# BpodFSM_r2_5_v6.net
KiCad netlist of a schematic drawn in EAGLE
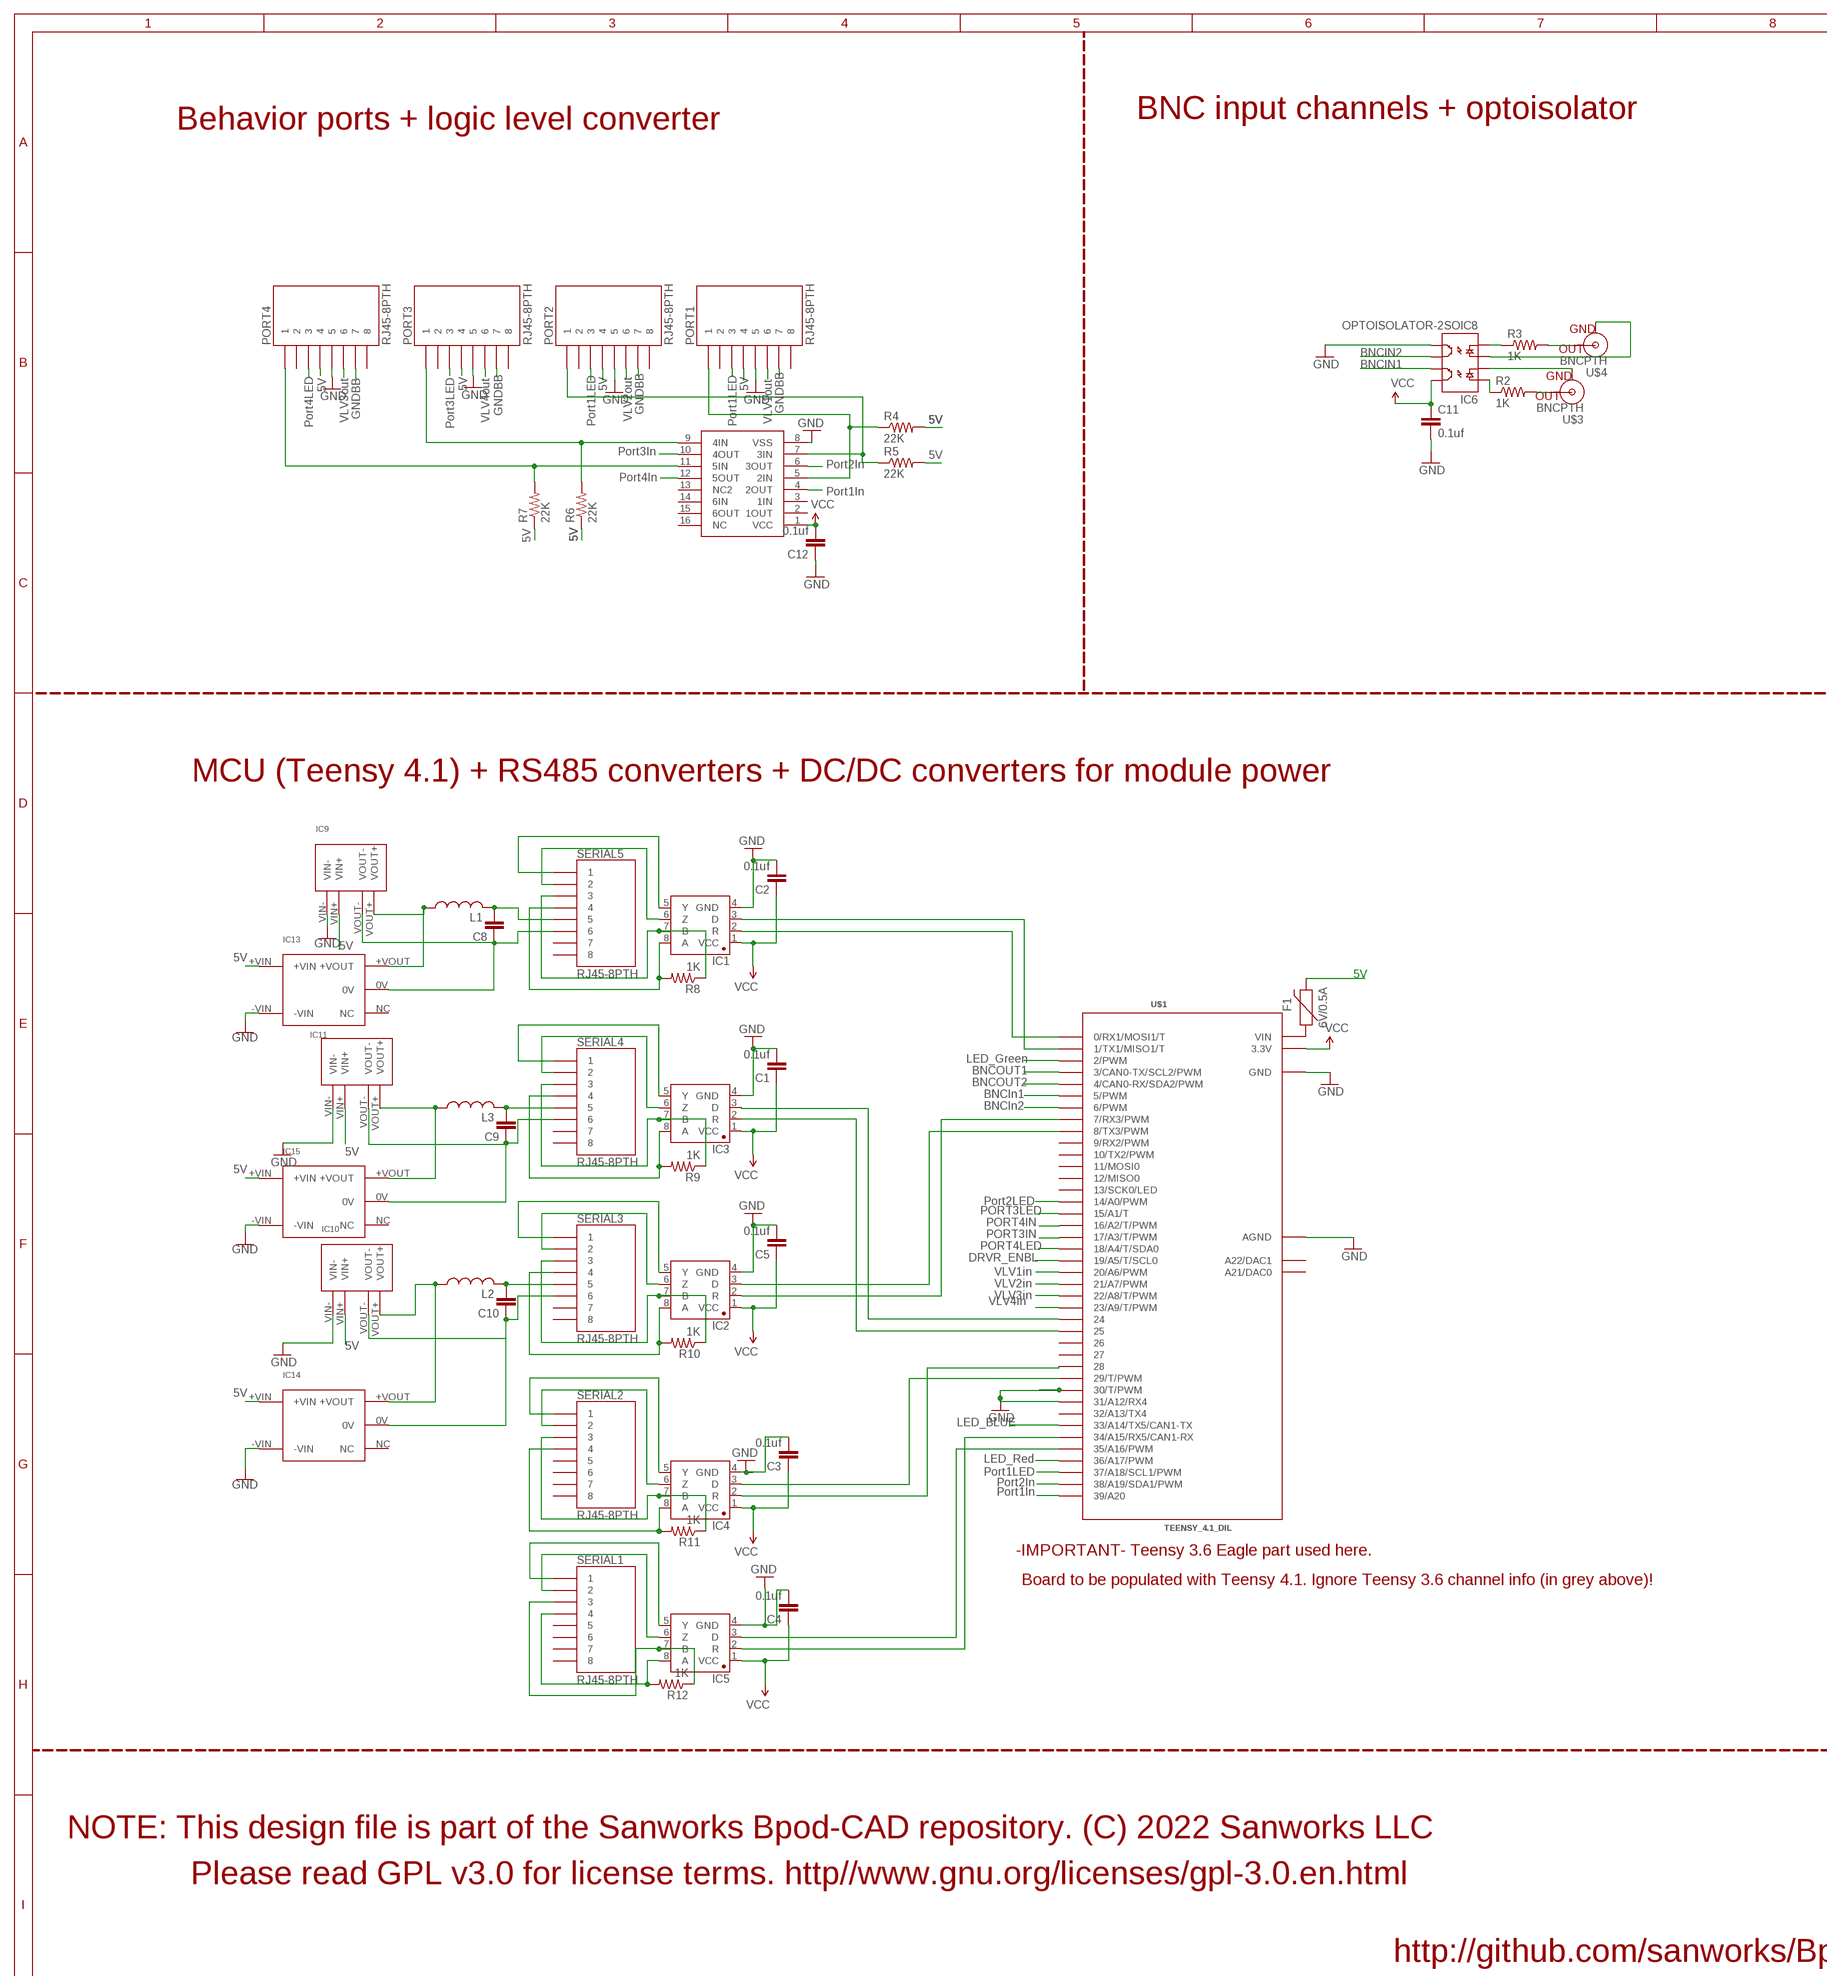
[diagram p0: schematic, sheet 1, part 1 of 2]
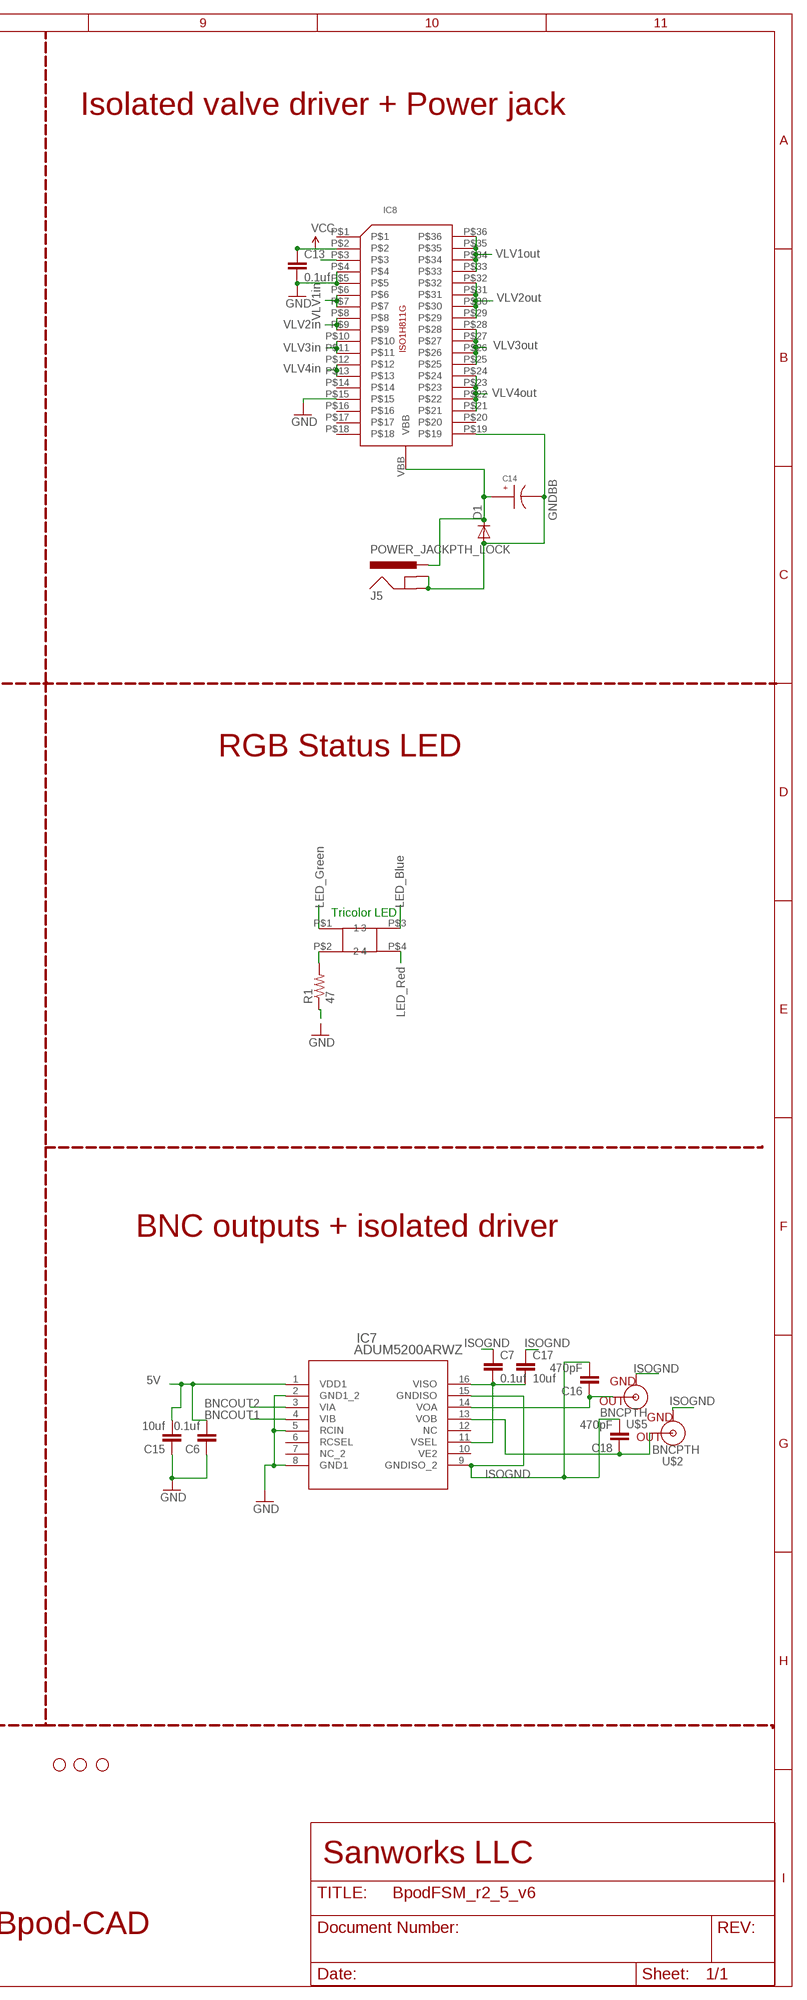
[diagram p1: schematic, sheet 1, part 2 of 2]

(export (version "E")
  (design (tool "Eeschema 10.0.6"))
  (components
    (comp (ref "C1")
      (value "0.1uf")
      (footprint "eagle-import:1206@1")
      (libsource (lib "eagle-import") (part "CAP1206"))
    )
    (comp (ref "C2")
      (value "0.1uf")
      (footprint "eagle-import:1206@1")
      (libsource (lib "eagle-import") (part "CAP1206"))
    )
    (comp (ref "C3")
      (value "0.1uf")
      (footprint "eagle-import:1206@1")
      (libsource (lib "eagle-import") (part "CAP1206"))
    )
    (comp (ref "C4")
      (value "0.1uf")
      (footprint "eagle-import:1206@1")
      (libsource (lib "eagle-import") (part "CAP1206"))
    )
    (comp (ref "C5")
      (value "0.1uf")
      (footprint "eagle-import:1206@1")
      (libsource (lib "eagle-import") (part "CAP1206"))
    )
    (comp (ref "C6")
      (value "0.1uf")
      (footprint "eagle-import:0805")
      (libsource (lib "eagle-import") (part "1.0UF-0805-25V-10%"))
    )
    (comp (ref "C7")
      (value "0.1uf")
      (footprint "eagle-import:0805")
      (libsource (lib "eagle-import") (part "1.0UF-0805-25V-10%"))
    )
    (comp (ref "C8")
      (value "CAP1206")
      (footprint "eagle-import:1206@1")
      (libsource (lib "eagle-import") (part "CAP1206"))
    )
    (comp (ref "C9")
      (value "CAP1206")
      (footprint "eagle-import:1206@1")
      (libsource (lib "eagle-import") (part "CAP1206"))
    )
    (comp (ref "C10")
      (value "CAP1206")
      (footprint "eagle-import:1206@1")
      (libsource (lib "eagle-import") (part "CAP1206"))
    )
    (comp (ref "C11")
      (value "0.1uf")
      (footprint "eagle-import:1206@1")
      (libsource (lib "eagle-import") (part "CAP1206"))
    )
    (comp (ref "C12")
      (value "0.1uf")
      (footprint "eagle-import:1206@1")
      (libsource (lib "eagle-import") (part "CAP1206"))
    )
    (comp (ref "C13")
      (value "0.1uf")
      (footprint "eagle-import:1206@1")
      (libsource (lib "eagle-import") (part "CAP1206"))
    )
    (comp (ref "C14")
      (value "EEE-FK1H100UR")
      (footprint "eagle-import:EEE-FK1H100UR")
      (libsource (lib "eagle-import") (part "EEE-FK1H100UR"))
    )
    (comp (ref "C15")
      (value "10uf")
      (footprint "eagle-import:1206@1")
      (libsource (lib "eagle-import") (part "CAP1206"))
    )
    (comp (ref "C16")
      (value "470pF")
      (footprint "eagle-import:0805")
      (libsource (lib "eagle-import") (part "1.0UF-0805-25V-10%"))
    )
    (comp (ref "C17")
      (value "10uf")
      (footprint "eagle-import:1206@1")
      (libsource (lib "eagle-import") (part "CAP1206"))
    )
    (comp (ref "C18")
      (value "470pF")
      (footprint "eagle-import:0805")
      (libsource (lib "eagle-import") (part "1.0UF-0805-25V-10%"))
    )
    (comp (ref "D1")
      (value "DIODE-DO214AA")
      (footprint "eagle-import:DO214AA")
      (libsource (lib "eagle-import") (part "DIODE-DO214AA"))
    )
    (comp (ref "F1")
      (value "6V/0.5A")
      (footprint "eagle-import:1206")
      (libsource (lib "eagle-import") (part "PPTC_HALF-AMP"))
    )
    (comp (ref "IC1")
      (value "SN65HVD31DR")
      (footprint "eagle-import:SO08")
      (libsource (lib "eagle-import") (part "SN65HVD31DR"))
    )
    (comp (ref "IC2")
      (value "SN65HVD31DR")
      (footprint "eagle-import:SO08")
      (libsource (lib "eagle-import") (part "SN65HVD31DR"))
    )
    (comp (ref "IC3")
      (value "SN65HVD31DR")
      (footprint "eagle-import:SO08")
      (libsource (lib "eagle-import") (part "SN65HVD31DR"))
    )
    (comp (ref "IC4")
      (value "SN65HVD31DR")
      (footprint "eagle-import:SO08")
      (libsource (lib "eagle-import") (part "SN65HVD31DR"))
    )
    (comp (ref "IC5")
      (value "SN65HVD31DR")
      (footprint "eagle-import:SO08")
      (libsource (lib "eagle-import") (part "SN65HVD31DR"))
    )
    (comp (ref "IC6")
      (value "OPTOISOLATOR-2SOIC8")
      (footprint "eagle-import:SO08-2")
      (libsource (lib "eagle-import") (part "OPTOISOLATOR-2SOIC8"))
    )
    (comp (ref "IC7")
      (value "ADUM5200ARWZ")
      (footprint "eagle-import:RW_16")
      (libsource (lib "eagle-import") (part "ADUM5200ARWZ"))
    )
    (comp (ref "IC8")
      (value "ISO1H811G")
      (footprint "eagle-import:ISO1H811G")
      (libsource (lib "eagle-import") (part "ISO1H811G"))
    )
    (comp (ref "IC9")
      (value "NME0509SC")
      (footprint "eagle-import:NME0509SC")
      (libsource (lib "eagle-import") (part "NME0509SC"))
    )
    (comp (ref "IC10")
      (value "NME0509SC")
      (footprint "eagle-import:NME0509SC")
      (libsource (lib "eagle-import") (part "NME0509SC"))
    )
    (comp (ref "IC11")
      (value "NME0509SC")
      (footprint "eagle-import:NME0509SC")
      (libsource (lib "eagle-import") (part "NME0509SC"))
    )
    (comp (ref "IC12")
      (value "CD4050")
      (footprint "eagle-import:SO16")
      (libsource (lib "eagle-import") (part "CD4050"))
    )
    (comp (ref "IC13")
      (value "MTU1D0505MC")
      (footprint "eagle-import:MTU1D0505MC")
      (libsource (lib "eagle-import") (part "MTU1D0505MC"))
    )
    (comp (ref "IC14")
      (value "MTU1D0505MC")
      (footprint "eagle-import:MTU1D0505MC")
      (libsource (lib "eagle-import") (part "MTU1D0505MC"))
    )
    (comp (ref "IC15")
      (value "MTU1D0505MC")
      (footprint "eagle-import:MTU1D0505MC")
      (libsource (lib "eagle-import") (part "MTU1D0505MC"))
    )
    (comp (ref "J5")
      (value "POWER_JACKPTH_LOCK")
      (footprint "eagle-import:POWER_JACK_PTH_LOCK")
      (libsource (lib "eagle-import") (part "POWER_JACKPTH_LOCK"))
    )
    (comp (ref "JP3")
      (value "STAND-OFF")
      (footprint "eagle-import:STAND-OFF")
      (libsource (lib "eagle-import") (part "STAND-OFF"))
    )
    (comp (ref "JP4")
      (value "STAND-OFF")
      (footprint "eagle-import:STAND-OFF")
      (libsource (lib "eagle-import") (part "STAND-OFF"))
    )
    (comp (ref "JP5")
      (value "STAND-OFF")
      (footprint "eagle-import:STAND-OFF")
      (libsource (lib "eagle-import") (part "STAND-OFF"))
    )
    (comp (ref "L1")
      (value "L-USL3225M")
      (footprint "eagle-import:L3225M")
      (libsource (lib "eagle-import") (part "L-USL3225M"))
    )
    (comp (ref "L2")
      (value "L-USL3225M")
      (footprint "eagle-import:L3225M")
      (libsource (lib "eagle-import") (part "L-USL3225M"))
    )
    (comp (ref "L3")
      (value "L-USL3225M")
      (footprint "eagle-import:L3225M")
      (libsource (lib "eagle-import") (part "L-USL3225M"))
    )
    (comp (ref "PORT1")
      (value "RJ45-8PTH")
      (footprint "eagle-import:RJ45-8")
      (libsource (lib "eagle-import") (part "RJ45-8PTH"))
    )
    (comp (ref "PORT2")
      (value "RJ45-8PTH")
      (footprint "eagle-import:RJ45-8")
      (libsource (lib "eagle-import") (part "RJ45-8PTH"))
    )
    (comp (ref "PORT3")
      (value "RJ45-8PTH")
      (footprint "eagle-import:RJ45-8")
      (libsource (lib "eagle-import") (part "RJ45-8PTH"))
    )
    (comp (ref "PORT4")
      (value "RJ45-8PTH")
      (footprint "eagle-import:RJ45-8")
      (libsource (lib "eagle-import") (part "RJ45-8PTH"))
    )
    (comp (ref "R1")
      (value "47")
      (footprint "eagle-import:1206")
      (libsource (lib "eagle-import") (part "RESISTOR1206"))
    )
    (comp (ref "R2")
      (value "1K")
      (footprint "eagle-import:1206")
      (libsource (lib "eagle-import") (part "SparkFun-Resistors_RESISTOR1206"))
    )
    (comp (ref "R3")
      (value "1K")
      (footprint "eagle-import:1206")
      (libsource (lib "eagle-import") (part "SparkFun-Resistors_RESISTOR1206"))
    )
    (comp (ref "R4")
      (value "22K")
      (footprint "eagle-import:1206")
      (libsource (lib "eagle-import") (part "SparkFun-Resistors_RESISTOR1206"))
    )
    (comp (ref "R5")
      (value "22K")
      (footprint "eagle-import:1206")
      (libsource (lib "eagle-import") (part "SparkFun-Resistors_RESISTOR1206"))
    )
    (comp (ref "R6")
      (value "22K")
      (footprint "eagle-import:1206")
      (libsource (lib "eagle-import") (part "SparkFun-Resistors_RESISTOR1206"))
    )
    (comp (ref "R7")
      (value "22K")
      (footprint "eagle-import:1206")
      (libsource (lib "eagle-import") (part "SparkFun-Resistors_RESISTOR1206"))
    )
    (comp (ref "R8")
      (value "1K")
      (footprint "eagle-import:1206")
      (libsource (lib "eagle-import") (part "SparkFun-Resistors_RESISTOR1206"))
    )
    (comp (ref "R9")
      (value "1K")
      (footprint "eagle-import:1206")
      (libsource (lib "eagle-import") (part "SparkFun-Resistors_RESISTOR1206"))
    )
    (comp (ref "R10")
      (value "1K")
      (footprint "eagle-import:1206")
      (libsource (lib "eagle-import") (part "SparkFun-Resistors_RESISTOR1206"))
    )
    (comp (ref "R11")
      (value "1K")
      (footprint "eagle-import:1206")
      (libsource (lib "eagle-import") (part "SparkFun-Resistors_RESISTOR1206"))
    )
    (comp (ref "R12")
      (value "1K")
      (footprint "eagle-import:1206")
      (libsource (lib "eagle-import") (part "SparkFun-Resistors_RESISTOR1206"))
    )
    (comp (ref "SERIAL1")
      (value "RJ45-8PTH")
      (footprint "eagle-import:RJ45-8")
      (libsource (lib "eagle-import") (part "RJ45-8PTH"))
    )
    (comp (ref "SERIAL2")
      (value "RJ45-8PTH")
      (footprint "eagle-import:RJ45-8")
      (libsource (lib "eagle-import") (part "RJ45-8PTH"))
    )
    (comp (ref "SERIAL3")
      (value "RJ45-8PTH")
      (footprint "eagle-import:RJ45-8")
      (libsource (lib "eagle-import") (part "RJ45-8PTH"))
    )
    (comp (ref "SERIAL4")
      (value "RJ45-8PTH")
      (footprint "eagle-import:RJ45-8")
      (libsource (lib "eagle-import") (part "RJ45-8PTH"))
    )
    (comp (ref "SERIAL5")
      (value "RJ45-8PTH")
      (footprint "eagle-import:RJ45-8")
      (libsource (lib "eagle-import") (part "RJ45-8PTH"))
    )
    (comp (ref "U$1")
      (value "TEENSY_4.1_DIL")
      (footprint "eagle-import:TEENSY_3.6_DIL")
      (libsource (lib "eagle-import") (part "TEENSY_3.6_DIL"))
    )
    (comp (ref "U$2")
      (value "BNCPTH")
      (footprint "eagle-import:BNC")
      (libsource (lib "eagle-import") (part "BNCPTH"))
    )
    (comp (ref "U$3")
      (value "BNCPTH")
      (footprint "eagle-import:BNC")
      (libsource (lib "eagle-import") (part "BNCPTH"))
    )
    (comp (ref "U$4")
      (value "BNCPTH")
      (footprint "eagle-import:BNC")
      (libsource (lib "eagle-import") (part "BNCPTH"))
    )
    (comp (ref "U$5")
      (value "BNCPTH")
      (footprint "eagle-import:BNC")
      (libsource (lib "eagle-import") (part "BNCPTH"))
    )
    (comp (ref "U$8")
      (value "SQUARE_TRICOLOR_LED")
      (footprint "eagle-import:SQUARE_TRICOLOR_LED")
      (libsource (lib "eagle-import") (part "SQUARE_TRICOLOR_LED"))
    )
  )
  (nets
    (net (code "1") (name "/5V") (class "Default")
      (node (ref "C15") (pin "2") (pinfunction "2_2") (pintype "passive"))
      (node (ref "C6") (pin "2") (pinfunction "2_2") (pintype "passive"))
      (node (ref "F1") (pin "2") (pinfunction "2_2") (pintype "bidirectional"))
      (node (ref "IC10") (pin "VIN+") (pinfunction "VIN+_VIN+") (pintype "bidirectional"))
      (node (ref "IC11") (pin "VIN+") (pinfunction "VIN+_VIN+") (pintype "bidirectional"))
      (node (ref "IC13") (pin "+VIN") (pinfunction "+VIN_+VIN") (pintype "bidirectional"))
      (node (ref "IC14") (pin "+VIN") (pinfunction "+VIN_+VIN") (pintype "bidirectional"))
      (node (ref "IC15") (pin "+VIN") (pinfunction "+VIN_+VIN") (pintype "bidirectional"))
      (node (ref "IC7") (pin "1") (pinfunction "VDD1_1") (pintype "passive"))
      (node (ref "IC9") (pin "VIN+") (pinfunction "VIN+_VIN+") (pintype "bidirectional"))
      (node (ref "PORT1") (pin "4") (pinfunction "4_4") (pintype "bidirectional"))
      (node (ref "PORT2") (pin "4") (pinfunction "4_4") (pintype "bidirectional"))
      (node (ref "PORT3") (pin "4") (pinfunction "4_4") (pintype "bidirectional"))
      (node (ref "PORT4") (pin "4") (pinfunction "4_4") (pintype "bidirectional"))
      (node (ref "R4") (pin "2") (pinfunction "2_2") (pintype "passive"))
      (node (ref "R5") (pin "2") (pinfunction "2_2") (pintype "passive"))
      (node (ref "R6") (pin "1") (pinfunction "1_1") (pintype "passive"))
      (node (ref "R7") (pin "1") (pinfunction "1_1") (pintype "passive"))
    )
    (net (code "2") (name "/BNCIN1") (class "Default")
      (node (ref "IC6") (pin "7") (pinfunction "EM1_7") (pintype "bidirectional"))
      (node (ref "U$1") (pin "6") (pinfunction "6/PWM_6") (pintype "bidirectional"))
    )
    (net (code "3") (name "/BNCIN2") (class "Default")
      (node (ref "IC6") (pin "6") (pinfunction "CL2_6") (pintype "bidirectional"))
      (node (ref "U$1") (pin "5") (pinfunction "5/PWM_5") (pintype "bidirectional"))
    )
    (net (code "4") (name "/BNCOUT1") (class "Default")
      (node (ref "IC7") (pin "4") (pinfunction "VIB_4") (pintype "passive"))
      (node (ref "U$1") (pin "4") (pinfunction "4/CAN0-RX/SDA2/PWM_4") (pintype "bidirectional"))
    )
    (net (code "5") (name "/BNCOUT2") (class "Default")
      (node (ref "IC7") (pin "3") (pinfunction "VIA_3") (pintype "passive"))
      (node (ref "U$1") (pin "3") (pinfunction "3/CAN0-TX/SCL2/PWM_3") (pintype "bidirectional"))
    )
    (net (code "6") (name "/DRVR_ENBL") (class "Default")
      (node (ref "IC8") (pin "P$3") (pinfunction "P$3_P$3") (pintype "bidirectional"))
      (node (ref "U$1") (pin "19/A5") (pinfunction "19/A5/T/SCL0_19/A5") (pintype "bidirectional"))
    )
    (net (code "7") (name "/GNDBB") (class "Default")
      (node (ref "C14") (pin "CATHODE") (pinfunction "CATHODE_CATHODE") (pintype "bidirectional"))
      (node (ref "D1") (pin "A") (pinfunction "A_A") (pintype "passive"))
      (node (ref "IC8") (pin "P$19") (pinfunction "P$19_P$19") (pintype "bidirectional"))
      (node (ref "J5") (pin "GND") (pinfunction "GND_GND") (pintype "bidirectional"))
      (node (ref "J5") (pin "GNDBREAK") (pinfunction "GNDBREAK_GNDBREAK") (pintype "bidirectional"))
      (node (ref "PORT1") (pin "7") (pinfunction "7_7") (pintype "bidirectional"))
      (node (ref "PORT2") (pin "7") (pinfunction "7_7") (pintype "bidirectional"))
      (node (ref "PORT3") (pin "7") (pinfunction "7_7") (pintype "bidirectional"))
      (node (ref "PORT4") (pin "7") (pinfunction "7_7") (pintype "bidirectional"))
    )
    (net (code "8") (name "/ISOGND") (class "Default")
      (node (ref "C16") (pin "2") (pinfunction "2_2") (pintype "passive"))
      (node (ref "C17") (pin "1") (pinfunction "1_1") (pintype "passive"))
      (node (ref "C18") (pin "2") (pinfunction "2_2") (pintype "passive"))
      (node (ref "C7") (pin "1") (pinfunction "1_1") (pintype "passive"))
      (node (ref "IC7") (pin "15") (pinfunction "GNDISO_15") (pintype "passive"))
      (node (ref "IC7") (pin "9") (pinfunction "GNDISO_2_9") (pintype "passive"))
      (node (ref "U$2") (pin "GND") (pinfunction "GND_GND") (pintype "bidirectional"))
      (node (ref "U$5") (pin "GND") (pinfunction "GND_GND") (pintype "bidirectional"))
    )
    (net (code "9") (name "/LED_BLUE") (class "Default")
      (node (ref "U$1") (pin "33/A14") (pinfunction "33/A14/TX5/CAN1-TX_33/A14") (pintype "bidirectional"))
      (node (ref "U$8") (pin "P$3") (pinfunction "3_P$3") (pintype "bidirectional"))
    )
    (net (code "10") (name "/LED_GREEN") (class "Default")
      (node (ref "U$1") (pin "2") (pinfunction "2/PWM_2") (pintype "bidirectional"))
      (node (ref "U$8") (pin "P$1") (pinfunction "1_P$1") (pintype "bidirectional"))
    )
    (net (code "11") (name "/LED_RED") (class "Default")
      (node (ref "U$1") (pin "36/A17") (pinfunction "36/A17/PWM_36/A17") (pintype "bidirectional"))
      (node (ref "U$8") (pin "P$4") (pinfunction "4_P$4") (pintype "bidirectional"))
    )
    (net (code "12") (name "/PORT1IN") (class "Default")
      (node (ref "IC12") (pin "4") (pinfunction "2OUT_4") (pintype "bidirectional"))
      (node (ref "U$1") (pin "39/A20") (pinfunction "39/A20_39/A20") (pintype "bidirectional"))
    )
    (net (code "13") (name "/PORT1LED") (class "Default")
      (node (ref "PORT1") (pin "3") (pinfunction "3_3") (pintype "bidirectional"))
      (node (ref "U$1") (pin "37/A18") (pinfunction "37/A18/SCL1/PWM_37/A18") (pintype "bidirectional"))
    )
    (net (code "14") (name "/PORT2IN") (class "Default")
      (node (ref "IC12") (pin "6") (pinfunction "3OUT_6") (pintype "bidirectional"))
      (node (ref "U$1") (pin "38/A19") (pinfunction "38/A19/SDA1/PWM_38/A19") (pintype "bidirectional"))
    )
    (net (code "15") (name "/PORT2LED") (class "Default")
      (node (ref "PORT2") (pin "3") (pinfunction "3_3") (pintype "bidirectional"))
      (node (ref "U$1") (pin "14/A0") (pinfunction "14/A0/PWM_14/A0") (pintype "bidirectional"))
    )
    (net (code "16") (name "/PORT3IN") (class "Default")
      (node (ref "IC12") (pin "10") (pinfunction "4OUT_10") (pintype "bidirectional"))
      (node (ref "U$1") (pin "17/A3") (pinfunction "17/A3/T/PWM_17/A3") (pintype "bidirectional"))
    )
    (net (code "17") (name "/PORT3LED") (class "Default")
      (node (ref "PORT3") (pin "3") (pinfunction "3_3") (pintype "bidirectional"))
      (node (ref "U$1") (pin "15/A1") (pinfunction "15/A1/T_15/A1") (pintype "bidirectional"))
    )
    (net (code "18") (name "/PORT4IN") (class "Default")
      (node (ref "IC12") (pin "12") (pinfunction "5OUT_12") (pintype "bidirectional"))
      (node (ref "U$1") (pin "16/A2") (pinfunction "16/A2/T/PWM_16/A2") (pintype "bidirectional"))
    )
    (net (code "19") (name "/PORT4LED") (class "Default")
      (node (ref "PORT4") (pin "3") (pinfunction "3_3") (pintype "bidirectional"))
      (node (ref "U$1") (pin "18/A4") (pinfunction "18/A4/T/SDA0_18/A4") (pintype "bidirectional"))
    )
    (net (code "20") (name "/VLV1IN") (class "Default")
      (node (ref "IC8") (pin "P$6") (pinfunction "P$6_P$6") (pintype "bidirectional"))
      (node (ref "IC8") (pin "P$7") (pinfunction "P$7_P$7") (pintype "bidirectional"))
      (node (ref "U$1") (pin "23/A9") (pinfunction "23/A9/T/PWM_23/A9") (pintype "bidirectional"))
    )
    (net (code "21") (name "/VLV1OUT") (class "Default")
      (node (ref "IC8") (pin "P$33") (pinfunction "P$33_P$33") (pintype "bidirectional"))
      (node (ref "IC8") (pin "P$34") (pinfunction "P$34_P$34") (pintype "bidirectional"))
      (node (ref "IC8") (pin "P$35") (pinfunction "P$35_P$35") (pintype "bidirectional"))
      (node (ref "IC8") (pin "P$36") (pinfunction "P$36_P$36") (pintype "bidirectional"))
      (node (ref "PORT1") (pin "6") (pinfunction "6_6") (pintype "bidirectional"))
    )
    (net (code "22") (name "/VLV2IN") (class "Default")
      (node (ref "IC8") (pin "P$8") (pinfunction "P$8_P$8") (pintype "bidirectional"))
      (node (ref "IC8") (pin "P$9") (pinfunction "P$9_P$9") (pintype "bidirectional"))
      (node (ref "U$1") (pin "22/A8") (pinfunction "22/A8/T/PWM_22/A8") (pintype "bidirectional"))
    )
    (net (code "23") (name "/VLV2OUT") (class "Default")
      (node (ref "IC8") (pin "P$29") (pinfunction "P$29_P$29") (pintype "bidirectional"))
      (node (ref "IC8") (pin "P$30") (pinfunction "P$30_P$30") (pintype "bidirectional"))
      (node (ref "IC8") (pin "P$31") (pinfunction "P$31_P$31") (pintype "bidirectional"))
      (node (ref "IC8") (pin "P$32") (pinfunction "P$32_P$32") (pintype "bidirectional"))
      (node (ref "PORT2") (pin "6") (pinfunction "6_6") (pintype "bidirectional"))
    )
    (net (code "24") (name "/VLV3IN") (class "Default")
      (node (ref "IC8") (pin "P$12") (pinfunction "P$12_P$12") (pintype "bidirectional"))
      (node (ref "IC8") (pin "P$13") (pinfunction "P$13_P$13") (pintype "bidirectional"))
      (node (ref "U$1") (pin "20/A6") (pinfunction "20/A6/PWM_20/A6") (pintype "bidirectional"))
    )
    (net (code "25") (name "/VLV3OUT") (class "Default")
      (node (ref "IC8") (pin "P$21") (pinfunction "P$21_P$21") (pintype "bidirectional"))
      (node (ref "IC8") (pin "P$22") (pinfunction "P$22_P$22") (pintype "bidirectional"))
      (node (ref "IC8") (pin "P$23") (pinfunction "P$23_P$23") (pintype "bidirectional"))
      (node (ref "IC8") (pin "P$24") (pinfunction "P$24_P$24") (pintype "bidirectional"))
      (node (ref "PORT3") (pin "6") (pinfunction "6_6") (pintype "bidirectional"))
    )
    (net (code "26") (name "/VLV4IN") (class "Default")
      (node (ref "IC8") (pin "P$10") (pinfunction "P$10_P$10") (pintype "bidirectional"))
      (node (ref "IC8") (pin "P$11") (pinfunction "P$11_P$11") (pintype "bidirectional"))
      (node (ref "U$1") (pin "21/A7") (pinfunction "21/A7/PWM_21/A7") (pintype "bidirectional"))
    )
    (net (code "27") (name "/VLV4OUT") (class "Default")
      (node (ref "IC8") (pin "P$25") (pinfunction "P$25_P$25") (pintype "bidirectional"))
      (node (ref "IC8") (pin "P$26") (pinfunction "P$26_P$26") (pintype "bidirectional"))
      (node (ref "IC8") (pin "P$27") (pinfunction "P$27_P$27") (pintype "bidirectional"))
      (node (ref "IC8") (pin "P$28") (pinfunction "P$28_P$28") (pintype "bidirectional"))
      (node (ref "PORT4") (pin "6") (pinfunction "6_6") (pintype "bidirectional"))
    )
    (net (code "28") (name "GND") (class "Default")
      (node (ref "C1") (pin "2") (pinfunction "2_2") (pintype "passive"))
      (node (ref "C11") (pin "2") (pinfunction "2_2") (pintype "passive"))
      (node (ref "C12") (pin "1") (pinfunction "1_1") (pintype "passive"))
      (node (ref "C13") (pin "2") (pinfunction "2_2") (pintype "passive"))
      (node (ref "C15") (pin "1") (pinfunction "1_1") (pintype "passive"))
      (node (ref "C2") (pin "2") (pinfunction "2_2") (pintype "passive"))
      (node (ref "C3") (pin "2") (pinfunction "2_2") (pintype "passive"))
      (node (ref "C4") (pin "2") (pinfunction "2_2") (pintype "passive"))
      (node (ref "C5") (pin "2") (pinfunction "2_2") (pintype "passive"))
      (node (ref "C6") (pin "1") (pinfunction "1_1") (pintype "passive"))
      (node (ref "IC1") (pin "4") (pinfunction "GND_4") (pintype "bidirectional"))
      (node (ref "IC10") (pin "VIN-") (pinfunction "VIN-_VIN-") (pintype "bidirectional"))
      (node (ref "IC11") (pin "VIN-") (pinfunction "VIN-_VIN-") (pintype "bidirectional"))
      (node (ref "IC12") (pin "8") (pinfunction "VSS_8") (pintype "bidirectional"))
      (node (ref "IC13") (pin "-VIN") (pinfunction "-VIN_-VIN") (pintype "bidirectional"))
      (node (ref "IC14") (pin "-VIN") (pinfunction "-VIN_-VIN") (pintype "bidirectional"))
      (node (ref "IC15") (pin "-VIN") (pinfunction "-VIN_-VIN") (pintype "bidirectional"))
      (node (ref "IC2") (pin "4") (pinfunction "GND_4") (pintype "bidirectional"))
      (node (ref "IC3") (pin "4") (pinfunction "GND_4") (pintype "bidirectional"))
      (node (ref "IC4") (pin "4") (pinfunction "GND_4") (pintype "bidirectional"))
      (node (ref "IC5") (pin "4") (pinfunction "GND_4") (pintype "bidirectional"))
      (node (ref "IC6") (pin "5") (pinfunction "EM2_5") (pintype "bidirectional"))
      (node (ref "IC7") (pin "2") (pinfunction "GND1_2_2") (pintype "passive"))
      (node (ref "IC7") (pin "5") (pinfunction "RCIN_5") (pintype "passive"))
      (node (ref "IC7") (pin "8") (pinfunction "GND1_8") (pintype "passive"))
      (node (ref "IC8") (pin "P$15") (pinfunction "P$15_P$15") (pintype "bidirectional"))
      (node (ref "IC8") (pin "P$4") (pinfunction "P$4_P$4") (pintype "bidirectional"))
      (node (ref "IC8") (pin "P$5") (pinfunction "P$5_P$5") (pintype "bidirectional"))
      (node (ref "IC9") (pin "VIN-") (pinfunction "VIN-_VIN-") (pintype "bidirectional"))
      (node (ref "PORT1") (pin "5") (pinfunction "5_5") (pintype "bidirectional"))
      (node (ref "PORT2") (pin "5") (pinfunction "5_5") (pintype "bidirectional"))
      (node (ref "PORT3") (pin "5") (pinfunction "5_5") (pintype "bidirectional"))
      (node (ref "PORT4") (pin "5") (pinfunction "5_5") (pintype "bidirectional"))
      (node (ref "R1") (pin "1") (pinfunction "1_1") (pintype "passive"))
      (node (ref "U$1") (pin "30") (pinfunction "30/T/PWM_30") (pintype "bidirectional"))
      (node (ref "U$1") (pin "31/A12") (pinfunction "31/A12/RX4_31/A12") (pintype "bidirectional"))
      (node (ref "U$1") (pin "AGND") (pinfunction "AGND_AGND") (pintype "power_in"))
      (node (ref "U$1") (pin "GND") (pinfunction "GND_GND") (pintype "power_in"))
      (node (ref "U$1") (pin "GND1") (pinfunction "GND_GND1") (pintype "power_in"))
    )
    (net (code "29") (name "Net-(C8-Pad1)") (class "Default")
      (node (ref "C8") (pin "1") (pinfunction "1_1") (pintype "passive"))
      (node (ref "IC13") (pin "0V") (pinfunction "0V_0V") (pintype "bidirectional"))
      (node (ref "IC9") (pin "VOUT-") (pinfunction "VOUT-_VOUT-") (pintype "bidirectional"))
      (node (ref "SERIAL5") (pin "6") (pinfunction "6_6") (pintype "bidirectional"))
    )
    (net (code "30") (name "Net-(C8-Pad2)") (class "Default")
      (node (ref "C8") (pin "2") (pinfunction "2_2") (pintype "passive"))
      (node (ref "L1") (pin "2") (pinfunction "2_2") (pintype "passive"))
      (node (ref "SERIAL5") (pin "5") (pinfunction "5_5") (pintype "bidirectional"))
    )
    (net (code "31") (name "Net-(C9-Pad1)") (class "Default")
      (node (ref "C9") (pin "1") (pinfunction "1_1") (pintype "passive"))
      (node (ref "IC11") (pin "VOUT-") (pinfunction "VOUT-_VOUT-") (pintype "bidirectional"))
      (node (ref "IC15") (pin "0V") (pinfunction "0V_0V") (pintype "bidirectional"))
      (node (ref "SERIAL4") (pin "6") (pinfunction "6_6") (pintype "bidirectional"))
    )
    (net (code "32") (name "Net-(C9-Pad2)") (class "Default")
      (node (ref "C9") (pin "2") (pinfunction "2_2") (pintype "passive"))
      (node (ref "L3") (pin "2") (pinfunction "2_2") (pintype "passive"))
      (node (ref "SERIAL4") (pin "5") (pinfunction "5_5") (pintype "bidirectional"))
    )
    (net (code "33") (name "Net-(C10-Pad1)") (class "Default")
      (node (ref "C10") (pin "1") (pinfunction "1_1") (pintype "passive"))
      (node (ref "IC10") (pin "VOUT-") (pinfunction "VOUT-_VOUT-") (pintype "bidirectional"))
      (node (ref "IC14") (pin "0V") (pinfunction "0V_0V") (pintype "bidirectional"))
      (node (ref "SERIAL3") (pin "6") (pinfunction "6_6") (pintype "bidirectional"))
    )
    (net (code "34") (name "Net-(C10-Pad2)") (class "Default")
      (node (ref "C10") (pin "2") (pinfunction "2_2") (pintype "passive"))
      (node (ref "L2") (pin "2") (pinfunction "2_2") (pintype "passive"))
      (node (ref "SERIAL3") (pin "5") (pinfunction "5_5") (pintype "bidirectional"))
    )
    (net (code "35") (name "Net-(C14-PadANODE)") (class "Default")
      (node (ref "C14") (pin "ANODE") (pinfunction "ANODE_ANODE") (pintype "bidirectional"))
      (node (ref "D1") (pin "C") (pinfunction "C_C") (pintype "passive"))
      (node (ref "IC8") (pin "VBB") (pinfunction "VBB_VBB") (pintype "bidirectional"))
      (node (ref "J5") (pin "PWR") (pinfunction "PWR_PWR") (pintype "bidirectional"))
    )
    (net (code "36") (name "Net-(F1-Pad1)") (class "Default")
      (node (ref "F1") (pin "1") (pinfunction "1_1") (pintype "bidirectional"))
      (node (ref "U$1") (pin "VIN") (pinfunction "VIN_VIN") (pintype "power_in"))
    )
    (net (code "37") (name "Net-(IC1-A)") (class "Default")
      (node (ref "IC1") (pin "8") (pinfunction "A_8") (pintype "bidirectional"))
      (node (ref "R8") (pin "2") (pinfunction "2_2") (pintype "passive"))
      (node (ref "SERIAL5") (pin "4") (pinfunction "4_4") (pintype "bidirectional"))
    )
    (net (code "38") (name "Net-(IC1-B)") (class "Default")
      (node (ref "IC1") (pin "7") (pinfunction "B_7") (pintype "bidirectional"))
      (node (ref "R8") (pin "1") (pinfunction "1_1") (pintype "passive"))
      (node (ref "SERIAL5") (pin "3") (pinfunction "3_3") (pintype "bidirectional"))
    )
    (net (code "39") (name "Net-(IC1-D)") (class "Default")
      (node (ref "IC1") (pin "3") (pinfunction "D_3") (pintype "bidirectional"))
      (node (ref "U$1") (pin "1") (pinfunction "1/TX1/MISO1/T_1") (pintype "bidirectional"))
    )
    (net (code "40") (name "Net-(IC1-R)") (class "Default")
      (node (ref "IC1") (pin "2") (pinfunction "R_2") (pintype "bidirectional"))
      (node (ref "U$1") (pin "0") (pinfunction "0/RX1/MOSI1/T_0") (pintype "bidirectional"))
    )
    (net (code "41") (name "Net-(IC1-Y)") (class "Default")
      (node (ref "IC1") (pin "5") (pinfunction "Y_5") (pintype "bidirectional"))
      (node (ref "SERIAL5") (pin "1") (pinfunction "1_1") (pintype "bidirectional"))
    )
    (net (code "42") (name "Net-(IC1-Z)") (class "Default")
      (node (ref "IC1") (pin "6") (pinfunction "Z_6") (pintype "bidirectional"))
      (node (ref "SERIAL5") (pin "2") (pinfunction "2_2") (pintype "bidirectional"))
    )
    (net (code "43") (name "Net-(IC2-A)") (class "Default")
      (node (ref "IC2") (pin "8") (pinfunction "A_8") (pintype "bidirectional"))
      (node (ref "R10") (pin "2") (pinfunction "2_2") (pintype "passive"))
      (node (ref "SERIAL3") (pin "4") (pinfunction "4_4") (pintype "bidirectional"))
    )
    (net (code "44") (name "Net-(IC2-B)") (class "Default")
      (node (ref "IC2") (pin "7") (pinfunction "B_7") (pintype "bidirectional"))
      (node (ref "R10") (pin "1") (pinfunction "1_1") (pintype "passive"))
      (node (ref "SERIAL3") (pin "3") (pinfunction "3_3") (pintype "bidirectional"))
    )
    (net (code "45") (name "Net-(IC2-D)") (class "Default")
      (node (ref "IC2") (pin "3") (pinfunction "D_3") (pintype "bidirectional"))
      (node (ref "U$1") (pin "8") (pinfunction "8/TX3/PWM_8") (pintype "bidirectional"))
    )
    (net (code "46") (name "Net-(IC2-R)") (class "Default")
      (node (ref "IC2") (pin "2") (pinfunction "R_2") (pintype "bidirectional"))
      (node (ref "U$1") (pin "7") (pinfunction "7/RX3/PWM_7") (pintype "bidirectional"))
    )
    (net (code "47") (name "Net-(IC2-Y)") (class "Default")
      (node (ref "IC2") (pin "5") (pinfunction "Y_5") (pintype "bidirectional"))
      (node (ref "SERIAL3") (pin "1") (pinfunction "1_1") (pintype "bidirectional"))
    )
    (net (code "48") (name "Net-(IC2-Z)") (class "Default")
      (node (ref "IC2") (pin "6") (pinfunction "Z_6") (pintype "bidirectional"))
      (node (ref "SERIAL3") (pin "2") (pinfunction "2_2") (pintype "bidirectional"))
    )
    (net (code "49") (name "Net-(IC3-A)") (class "Default")
      (node (ref "IC3") (pin "8") (pinfunction "A_8") (pintype "bidirectional"))
      (node (ref "R9") (pin "2") (pinfunction "2_2") (pintype "passive"))
      (node (ref "SERIAL4") (pin "4") (pinfunction "4_4") (pintype "bidirectional"))
    )
    (net (code "50") (name "Net-(IC3-B)") (class "Default")
      (node (ref "IC3") (pin "7") (pinfunction "B_7") (pintype "bidirectional"))
      (node (ref "R9") (pin "1") (pinfunction "1_1") (pintype "passive"))
      (node (ref "SERIAL4") (pin "3") (pinfunction "3_3") (pintype "bidirectional"))
    )
    (net (code "51") (name "Net-(IC3-D)") (class "Default")
      (node (ref "IC3") (pin "3") (pinfunction "D_3") (pintype "bidirectional"))
      (node (ref "U$1") (pin "24") (pinfunction "24_24") (pintype "bidirectional"))
    )
    (net (code "52") (name "Net-(IC3-R)") (class "Default")
      (node (ref "IC3") (pin "2") (pinfunction "R_2") (pintype "bidirectional"))
      (node (ref "U$1") (pin "25") (pinfunction "25_25") (pintype "bidirectional"))
    )
    (net (code "53") (name "Net-(IC3-Y)") (class "Default")
      (node (ref "IC3") (pin "5") (pinfunction "Y_5") (pintype "bidirectional"))
      (node (ref "SERIAL4") (pin "1") (pinfunction "1_1") (pintype "bidirectional"))
    )
    (net (code "54") (name "Net-(IC3-Z)") (class "Default")
      (node (ref "IC3") (pin "6") (pinfunction "Z_6") (pintype "bidirectional"))
      (node (ref "SERIAL4") (pin "2") (pinfunction "2_2") (pintype "bidirectional"))
    )
    (net (code "55") (name "Net-(IC4-A)") (class "Default")
      (node (ref "IC4") (pin "8") (pinfunction "A_8") (pintype "bidirectional"))
      (node (ref "R11") (pin "2") (pinfunction "2_2") (pintype "passive"))
      (node (ref "SERIAL2") (pin "4") (pinfunction "4_4") (pintype "bidirectional"))
    )
    (net (code "56") (name "Net-(IC4-B)") (class "Default")
      (node (ref "IC4") (pin "7") (pinfunction "B_7") (pintype "bidirectional"))
      (node (ref "R11") (pin "1") (pinfunction "1_1") (pintype "passive"))
      (node (ref "SERIAL2") (pin "3") (pinfunction "3_3") (pintype "bidirectional"))
    )
    (net (code "57") (name "Net-(IC4-D)") (class "Default")
      (node (ref "IC4") (pin "3") (pinfunction "D_3") (pintype "bidirectional"))
      (node (ref "U$1") (pin "29") (pinfunction "29/T/PWM_29") (pintype "bidirectional"))
    )
    (net (code "58") (name "Net-(IC4-R)") (class "Default")
      (node (ref "IC4") (pin "2") (pinfunction "R_2") (pintype "bidirectional"))
      (node (ref "U$1") (pin "28") (pinfunction "28_28") (pintype "bidirectional"))
    )
    (net (code "59") (name "Net-(IC4-Y)") (class "Default")
      (node (ref "IC4") (pin "5") (pinfunction "Y_5") (pintype "bidirectional"))
      (node (ref "SERIAL2") (pin "1") (pinfunction "1_1") (pintype "bidirectional"))
    )
    (net (code "60") (name "Net-(IC4-Z)") (class "Default")
      (node (ref "IC4") (pin "6") (pinfunction "Z_6") (pintype "bidirectional"))
      (node (ref "SERIAL2") (pin "2") (pinfunction "2_2") (pintype "bidirectional"))
    )
    (net (code "61") (name "Net-(IC5-A)") (class "Default")
      (node (ref "IC5") (pin "8") (pinfunction "A_8") (pintype "bidirectional"))
      (node (ref "R12") (pin "2") (pinfunction "2_2") (pintype "passive"))
      (node (ref "SERIAL1") (pin "4") (pinfunction "4_4") (pintype "bidirectional"))
    )
    (net (code "62") (name "Net-(IC5-B)") (class "Default")
      (node (ref "IC5") (pin "7") (pinfunction "B_7") (pintype "bidirectional"))
      (node (ref "R12") (pin "1") (pinfunction "1_1") (pintype "passive"))
      (node (ref "SERIAL1") (pin "3") (pinfunction "3_3") (pintype "bidirectional"))
    )
    (net (code "63") (name "Net-(IC5-D)") (class "Default")
      (node (ref "IC5") (pin "3") (pinfunction "D_3") (pintype "bidirectional"))
      (node (ref "U$1") (pin "35/A16") (pinfunction "35/A16/PWM_35/A16") (pintype "bidirectional"))
    )
    (net (code "64") (name "Net-(IC5-R)") (class "Default")
      (node (ref "IC5") (pin "2") (pinfunction "R_2") (pintype "bidirectional"))
      (node (ref "U$1") (pin "34/A15") (pinfunction "34/A15/RX5/CAN1-RX_34/A15") (pintype "bidirectional"))
    )
    (net (code "65") (name "Net-(IC5-Y)") (class "Default")
      (node (ref "IC5") (pin "5") (pinfunction "Y_5") (pintype "bidirectional"))
      (node (ref "SERIAL1") (pin "1") (pinfunction "1_1") (pintype "bidirectional"))
    )
    (net (code "66") (name "Net-(IC5-Z)") (class "Default")
      (node (ref "IC5") (pin "6") (pinfunction "Z_6") (pintype "bidirectional"))
      (node (ref "SERIAL1") (pin "2") (pinfunction "2_2") (pintype "bidirectional"))
    )
    (net (code "67") (name "Net-(IC6-A1)") (class "Default")
      (node (ref "IC6") (pin "1") (pinfunction "A1_1") (pintype "bidirectional"))
      (node (ref "R2") (pin "1") (pinfunction "1_1") (pintype "passive"))
    )
    (net (code "68") (name "Net-(IC6-A2)") (class "Default")
      (node (ref "IC6") (pin "3") (pinfunction "A2_3") (pintype "bidirectional"))
      (node (ref "U$4") (pin "GND") (pinfunction "GND_GND") (pintype "bidirectional"))
    )
    (net (code "69") (name "Net-(IC6-C1)") (class "Default")
      (node (ref "IC6") (pin "2") (pinfunction "C1_2") (pintype "bidirectional"))
      (node (ref "U$3") (pin "GND") (pinfunction "GND_GND") (pintype "bidirectional"))
    )
    (net (code "70") (name "Net-(IC6-C2)") (class "Default")
      (node (ref "IC6") (pin "4") (pinfunction "C2_4") (pintype "bidirectional"))
      (node (ref "R3") (pin "1") (pinfunction "1_1") (pintype "passive"))
    )
    (net (code "71") (name "Net-(IC7-VISO)") (class "Default")
      (node (ref "C17") (pin "2") (pinfunction "2_2") (pintype "passive"))
      (node (ref "C7") (pin "2") (pinfunction "2_2") (pintype "passive"))
      (node (ref "IC7") (pin "11") (pinfunction "VSEL_11") (pintype "passive"))
      (node (ref "IC7") (pin "16") (pinfunction "VISO_16") (pintype "passive"))
    )
    (net (code "72") (name "Net-(IC7-VOA)") (class "Default")
      (node (ref "C16") (pin "1") (pinfunction "1_1") (pintype "passive"))
      (node (ref "IC7") (pin "14") (pinfunction "VOA_14") (pintype "passive"))
      (node (ref "U$5") (pin "S") (pinfunction "OUT_S") (pintype "bidirectional"))
    )
    (net (code "73") (name "Net-(IC7-VOB)") (class "Default")
      (node (ref "C18") (pin "1") (pinfunction "1_1") (pintype "passive"))
      (node (ref "IC7") (pin "13") (pinfunction "VOB_13") (pintype "passive"))
      (node (ref "U$2") (pin "S") (pinfunction "OUT_S") (pintype "bidirectional"))
    )
    (net (code "74") (name "Net-(IC10-PadVOUT+)") (class "Default")
      (node (ref "IC10") (pin "VOUT+") (pinfunction "VOUT+_VOUT+") (pintype "bidirectional"))
      (node (ref "IC14") (pin "+VOUT") (pinfunction "+VOUT_+VOUT") (pintype "bidirectional"))
      (node (ref "L2") (pin "1") (pinfunction "1_1") (pintype "passive"))
    )
    (net (code "75") (name "Net-(IC11-PadVOUT+)") (class "Default")
      (node (ref "IC11") (pin "VOUT+") (pinfunction "VOUT+_VOUT+") (pintype "bidirectional"))
      (node (ref "IC15") (pin "+VOUT") (pinfunction "+VOUT_+VOUT") (pintype "bidirectional"))
      (node (ref "L3") (pin "1") (pinfunction "1_1") (pintype "passive"))
    )
    (net (code "76") (name "Net-(IC12-2IN)") (class "Default")
      (node (ref "IC12") (pin "5") (pinfunction "2IN_5") (pintype "bidirectional"))
      (node (ref "PORT1") (pin "1") (pinfunction "1_1") (pintype "bidirectional"))
      (node (ref "R4") (pin "1") (pinfunction "1_1") (pintype "passive"))
    )
    (net (code "77") (name "Net-(IC12-3IN)") (class "Default")
      (node (ref "IC12") (pin "7") (pinfunction "3IN_7") (pintype "bidirectional"))
      (node (ref "PORT2") (pin "1") (pinfunction "1_1") (pintype "bidirectional"))
      (node (ref "R5") (pin "1") (pinfunction "1_1") (pintype "passive"))
    )
    (net (code "78") (name "Net-(IC12-4IN)") (class "Default")
      (node (ref "IC12") (pin "9") (pinfunction "4IN_9") (pintype "bidirectional"))
      (node (ref "PORT3") (pin "1") (pinfunction "1_1") (pintype "bidirectional"))
      (node (ref "R6") (pin "2") (pinfunction "2_2") (pintype "passive"))
    )
    (net (code "79") (name "Net-(IC12-5IN)") (class "Default")
      (node (ref "IC12") (pin "11") (pinfunction "5IN_11") (pintype "bidirectional"))
      (node (ref "PORT4") (pin "1") (pinfunction "1_1") (pintype "bidirectional"))
      (node (ref "R7") (pin "2") (pinfunction "2_2") (pintype "passive"))
    )
    (net (code "80") (name "Net-(IC13-Pad+VOUT)") (class "Default")
      (node (ref "IC13") (pin "+VOUT") (pinfunction "+VOUT_+VOUT") (pintype "bidirectional"))
      (node (ref "IC9") (pin "VOUT+") (pinfunction "VOUT+_VOUT+") (pintype "bidirectional"))
      (node (ref "L1") (pin "1") (pinfunction "1_1") (pintype "passive"))
    )
    (net (code "81") (name "Net-(U$3-OUT)") (class "Default")
      (node (ref "R2") (pin "2") (pinfunction "2_2") (pintype "passive"))
      (node (ref "U$3") (pin "S") (pinfunction "OUT_S") (pintype "bidirectional"))
    )
    (net (code "82") (name "Net-(U$4-OUT)") (class "Default")
      (node (ref "R3") (pin "2") (pinfunction "2_2") (pintype "passive"))
      (node (ref "U$4") (pin "S") (pinfunction "OUT_S") (pintype "bidirectional"))
    )
    (net (code "83") (name "Net-(U$8-2)") (class "Default")
      (node (ref "R1") (pin "2") (pinfunction "2_2") (pintype "passive"))
      (node (ref "U$8") (pin "P$2") (pinfunction "2_P$2") (pintype "bidirectional"))
    )
    (net (code "84") (name "VCC") (class "Default")
      (node (ref "C1") (pin "1") (pinfunction "1_1") (pintype "passive"))
      (node (ref "C11") (pin "1") (pinfunction "1_1") (pintype "passive"))
      (node (ref "C12") (pin "2") (pinfunction "2_2") (pintype "passive"))
      (node (ref "C13") (pin "1") (pinfunction "1_1") (pintype "passive"))
      (node (ref "C2") (pin "1") (pinfunction "1_1") (pintype "passive"))
      (node (ref "C3") (pin "1") (pinfunction "1_1") (pintype "passive"))
      (node (ref "C4") (pin "1") (pinfunction "1_1") (pintype "passive"))
      (node (ref "C5") (pin "1") (pinfunction "1_1") (pintype "passive"))
      (node (ref "IC1") (pin "1") (pinfunction "VCC_1") (pintype "bidirectional"))
      (node (ref "IC12") (pin "1") (pinfunction "VCC_1") (pintype "bidirectional"))
      (node (ref "IC2") (pin "1") (pinfunction "VCC_1") (pintype "bidirectional"))
      (node (ref "IC3") (pin "1") (pinfunction "VCC_1") (pintype "bidirectional"))
      (node (ref "IC4") (pin "1") (pinfunction "VCC_1") (pintype "bidirectional"))
      (node (ref "IC5") (pin "1") (pinfunction "VCC_1") (pintype "bidirectional"))
      (node (ref "IC6") (pin "8") (pinfunction "CL1_8") (pintype "bidirectional"))
      (node (ref "IC8") (pin "P$2") (pinfunction "P$2_P$2") (pintype "bidirectional"))
      (node (ref "U$1") (pin "3.3V") (pinfunction "3.3V_3.3V") (pintype "power_in"))
      (node (ref "U$1") (pin "3.3V3") (pinfunction "3.3V_3.3V3") (pintype "power_in"))
    )
    (net (code "85") (name "unconnected-(IC7-NC-Pad12)") (class "Default")
      (node (ref "IC7") (pin "12") (pinfunction "NC_12") (pintype "passive"))
    )
    (net (code "86") (name "unconnected-(IC7-NC_2-Pad7)") (class "Default")
      (node (ref "IC7") (pin "7") (pinfunction "NC_2_7") (pintype "passive"))
    )
    (net (code "87") (name "unconnected-(IC7-RCSEL-Pad6)") (class "Default")
      (node (ref "IC7") (pin "6") (pinfunction "RCSEL_6") (pintype "passive"))
    )
    (net (code "88") (name "unconnected-(IC7-VE2-Pad10)") (class "Default")
      (node (ref "IC7") (pin "10") (pinfunction "VE2_10") (pintype "passive"))
    )
    (net (code "89") (name "unconnected-(IC8-PadP$1)") (class "Default")
      (node (ref "IC8") (pin "P$1") (pinfunction "P$1_P$1") (pintype "bidirectional"))
    )
    (net (code "90") (name "unconnected-(IC8-PadP$14)") (class "Default")
      (node (ref "IC8") (pin "P$14") (pinfunction "P$14_P$14") (pintype "bidirectional"))
    )
    (net (code "91") (name "unconnected-(IC8-PadP$16)") (class "Default")
      (node (ref "IC8") (pin "P$16") (pinfunction "P$16_P$16") (pintype "bidirectional"))
    )
    (net (code "92") (name "unconnected-(IC8-PadP$17)") (class "Default")
      (node (ref "IC8") (pin "P$17") (pinfunction "P$17_P$17") (pintype "bidirectional"))
    )
    (net (code "93") (name "unconnected-(IC8-PadP$18)") (class "Default")
      (node (ref "IC8") (pin "P$18") (pinfunction "P$18_P$18") (pintype "bidirectional"))
    )
    (net (code "94") (name "unconnected-(IC8-PadP$20)") (class "Default")
      (node (ref "IC8") (pin "P$20") (pinfunction "P$20_P$20") (pintype "bidirectional"))
    )
    (net (code "95") (name "unconnected-(IC12-1IN-Pad3)") (class "Default")
      (node (ref "IC12") (pin "3") (pinfunction "1IN_3") (pintype "bidirectional"))
    )
    (net (code "96") (name "unconnected-(IC12-1OUT-Pad2)") (class "Default")
      (node (ref "IC12") (pin "2") (pinfunction "1OUT_2") (pintype "bidirectional"))
    )
    (net (code "97") (name "unconnected-(IC12-6IN-Pad14)") (class "Default")
      (node (ref "IC12") (pin "14") (pinfunction "6IN_14") (pintype "bidirectional"))
    )
    (net (code "98") (name "unconnected-(IC12-6OUT-Pad15)") (class "Default")
      (node (ref "IC12") (pin "15") (pinfunction "6OUT_15") (pintype "bidirectional"))
    )
    (net (code "99") (name "unconnected-(IC12-NC-Pad16)") (class "Default")
      (node (ref "IC12") (pin "16") (pinfunction "NC_16") (pintype "bidirectional"))
    )
    (net (code "100") (name "unconnected-(IC12-NC2-Pad13)") (class "Default")
      (node (ref "IC12") (pin "13") (pinfunction "NC2_13") (pintype "bidirectional"))
    )
    (net (code "101") (name "unconnected-(IC13-PadNC)") (class "Default")
      (node (ref "IC13") (pin "NC") (pinfunction "NC_NC") (pintype "bidirectional"))
    )
    (net (code "102") (name "unconnected-(IC14-PadNC)") (class "Default")
      (node (ref "IC14") (pin "NC") (pinfunction "NC_NC") (pintype "bidirectional"))
    )
    (net (code "103") (name "unconnected-(IC15-PadNC)") (class "Default")
      (node (ref "IC15") (pin "NC") (pinfunction "NC_NC") (pintype "bidirectional"))
    )
    (net (code "104") (name "unconnected-(PORT1-Pad2)") (class "Default")
      (node (ref "PORT1") (pin "2") (pinfunction "2_2") (pintype "bidirectional"))
    )
    (net (code "105") (name "unconnected-(PORT1-Pad8)") (class "Default")
      (node (ref "PORT1") (pin "8") (pinfunction "8_8") (pintype "bidirectional"))
    )
    (net (code "106") (name "unconnected-(PORT2-Pad2)") (class "Default")
      (node (ref "PORT2") (pin "2") (pinfunction "2_2") (pintype "bidirectional"))
    )
    (net (code "107") (name "unconnected-(PORT2-Pad8)") (class "Default")
      (node (ref "PORT2") (pin "8") (pinfunction "8_8") (pintype "bidirectional"))
    )
    (net (code "108") (name "unconnected-(PORT3-Pad2)") (class "Default")
      (node (ref "PORT3") (pin "2") (pinfunction "2_2") (pintype "bidirectional"))
    )
    (net (code "109") (name "unconnected-(PORT3-Pad8)") (class "Default")
      (node (ref "PORT3") (pin "8") (pinfunction "8_8") (pintype "bidirectional"))
    )
    (net (code "110") (name "unconnected-(PORT4-Pad2)") (class "Default")
      (node (ref "PORT4") (pin "2") (pinfunction "2_2") (pintype "bidirectional"))
    )
    (net (code "111") (name "unconnected-(PORT4-Pad8)") (class "Default")
      (node (ref "PORT4") (pin "8") (pinfunction "8_8") (pintype "bidirectional"))
    )
    (net (code "112") (name "unconnected-(SERIAL1-Pad5)") (class "Default")
      (node (ref "SERIAL1") (pin "5") (pinfunction "5_5") (pintype "bidirectional"))
    )
    (net (code "113") (name "unconnected-(SERIAL1-Pad6)") (class "Default")
      (node (ref "SERIAL1") (pin "6") (pinfunction "6_6") (pintype "bidirectional"))
    )
    (net (code "114") (name "unconnected-(SERIAL1-Pad7)") (class "Default")
      (node (ref "SERIAL1") (pin "7") (pinfunction "7_7") (pintype "bidirectional"))
    )
    (net (code "115") (name "unconnected-(SERIAL1-Pad8)") (class "Default")
      (node (ref "SERIAL1") (pin "8") (pinfunction "8_8") (pintype "bidirectional"))
    )
    (net (code "116") (name "unconnected-(SERIAL2-Pad5)") (class "Default")
      (node (ref "SERIAL2") (pin "5") (pinfunction "5_5") (pintype "bidirectional"))
    )
    (net (code "117") (name "unconnected-(SERIAL2-Pad6)") (class "Default")
      (node (ref "SERIAL2") (pin "6") (pinfunction "6_6") (pintype "bidirectional"))
    )
    (net (code "118") (name "unconnected-(SERIAL2-Pad7)") (class "Default")
      (node (ref "SERIAL2") (pin "7") (pinfunction "7_7") (pintype "bidirectional"))
    )
    (net (code "119") (name "unconnected-(SERIAL2-Pad8)") (class "Default")
      (node (ref "SERIAL2") (pin "8") (pinfunction "8_8") (pintype "bidirectional"))
    )
    (net (code "120") (name "unconnected-(SERIAL3-Pad7)") (class "Default")
      (node (ref "SERIAL3") (pin "7") (pinfunction "7_7") (pintype "bidirectional"))
    )
    (net (code "121") (name "unconnected-(SERIAL3-Pad8)") (class "Default")
      (node (ref "SERIAL3") (pin "8") (pinfunction "8_8") (pintype "bidirectional"))
    )
    (net (code "122") (name "unconnected-(SERIAL4-Pad7)") (class "Default")
      (node (ref "SERIAL4") (pin "7") (pinfunction "7_7") (pintype "bidirectional"))
    )
    (net (code "123") (name "unconnected-(SERIAL4-Pad8)") (class "Default")
      (node (ref "SERIAL4") (pin "8") (pinfunction "8_8") (pintype "bidirectional"))
    )
    (net (code "124") (name "unconnected-(SERIAL5-Pad7)") (class "Default")
      (node (ref "SERIAL5") (pin "7") (pinfunction "7_7") (pintype "bidirectional"))
    )
    (net (code "125") (name "unconnected-(SERIAL5-Pad8)") (class "Default")
      (node (ref "SERIAL5") (pin "8") (pinfunction "8_8") (pintype "bidirectional"))
    )
    (net (code "126") (name "unconnected-(U$1-9{slash}RX2{slash}PWM-Pad9)") (class "Default")
      (node (ref "U$1") (pin "9") (pinfunction "9/RX2/PWM_9") (pintype "bidirectional"))
    )
    (net (code "127") (name "unconnected-(U$1-10{slash}TX2{slash}PWM-Pad10)") (class "Default")
      (node (ref "U$1") (pin "10") (pinfunction "10/TX2/PWM_10") (pintype "bidirectional"))
    )
    (net (code "128") (name "unconnected-(U$1-11{slash}MOSI0-Pad11)") (class "Default")
      (node (ref "U$1") (pin "11") (pinfunction "11/MOSI0_11") (pintype "bidirectional"))
    )
    (net (code "129") (name "unconnected-(U$1-12{slash}MISO0-Pad12)") (class "Default")
      (node (ref "U$1") (pin "12") (pinfunction "12/MISO0_12") (pintype "bidirectional"))
    )
    (net (code "130") (name "unconnected-(U$1-13{slash}SCK0{slash}LED-Pad13)") (class "Default")
      (node (ref "U$1") (pin "13") (pinfunction "13/SCK0/LED_13") (pintype "bidirectional"))
    )
    (net (code "131") (name "unconnected-(U$1-32{slash}A13{slash}TX4-Pad32{slash}A13)") (class "Default")
      (node (ref "U$1") (pin "32/A13") (pinfunction "32/A13/TX4_32/A13") (pintype "bidirectional"))
    )
    (net (code "132") (name "unconnected-(U$1-A21{slash}DAC0-PadA21)") (class "Default")
      (node (ref "U$1") (pin "A21") (pinfunction "A21/DAC0_A21") (pintype "bidirectional"))
    )
    (net (code "133") (name "unconnected-(U$1-A22{slash}DAC1-PadA22)") (class "Default")
      (node (ref "U$1") (pin "A22") (pinfunction "A22/DAC1_A22") (pintype "bidirectional"))
    )
    (net (code "134") (name "unconnected-(U$1-Pad26)") (class "Default")
      (node (ref "U$1") (pin "26") (pinfunction "26_26") (pintype "bidirectional"))
    )
    (net (code "135") (name "unconnected-(U$1-Pad27)") (class "Default")
      (node (ref "U$1") (pin "27") (pinfunction "27_27") (pintype "bidirectional"))
    )
  )
)
